# JoyStickBus.net
KiCad netlist of a schematic drawn in EAGLE
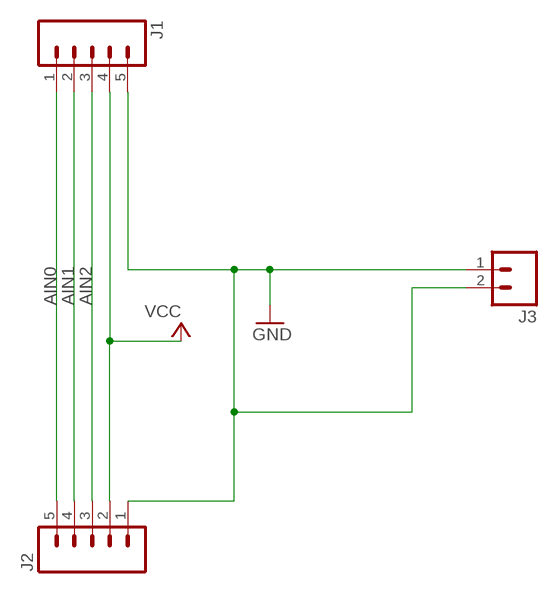
[diagram p0: schematic, sheet 1]

(export (version "E")
  (design (tool "Eeschema 10.0.6"))
  (components
    (comp (ref "J1")
      (value "M05NO_SILK")
      (footprint "eagle-import:1X05_NO_SILK")
      (libsource (lib "eagle-import") (part "M05NO_SILK"))
    )
    (comp (ref "J2")
      (value "M05NO_SILK")
      (footprint "eagle-import:1X05_NO_SILK")
      (libsource (lib "eagle-import") (part "M05NO_SILK"))
    )
    (comp (ref "J3")
      (value "M021X02_NO_SILK")
      (footprint "eagle-import:1X02_NO_SILK")
      (libsource (lib "eagle-import") (part "M021X02_NO_SILK"))
    )
  )
  (nets
    (net (code "1") (name "/AIN0") (class "Default")
      (node (ref "J1") (pin "1") (pinfunction "1_1") (pintype "passive"))
      (node (ref "J2") (pin "5") (pinfunction "5_5") (pintype "passive"))
    )
    (net (code "2") (name "/AIN1") (class "Default")
      (node (ref "J1") (pin "2") (pinfunction "2_2") (pintype "passive"))
      (node (ref "J2") (pin "4") (pinfunction "4_4") (pintype "passive"))
    )
    (net (code "3") (name "/AIN2") (class "Default")
      (node (ref "J1") (pin "3") (pinfunction "3_3") (pintype "passive"))
      (node (ref "J2") (pin "3") (pinfunction "3_3") (pintype "passive"))
    )
    (net (code "4") (name "GND") (class "Default")
      (node (ref "J1") (pin "5") (pinfunction "5_5") (pintype "passive"))
      (node (ref "J2") (pin "1") (pinfunction "1_1") (pintype "passive"))
      (node (ref "J3") (pin "1") (pinfunction "1_1") (pintype "passive"))
      (node (ref "J3") (pin "2") (pinfunction "2_2") (pintype "passive"))
    )
    (net (code "5") (name "VCC") (class "Default")
      (node (ref "J1") (pin "4") (pinfunction "4_4") (pintype "passive"))
      (node (ref "J2") (pin "2") (pinfunction "2_2") (pintype "passive"))
    )
  )
)
